# Nixie4_IN-1A_1_0.net
KiCad netlist of a schematic drawn in EAGLE
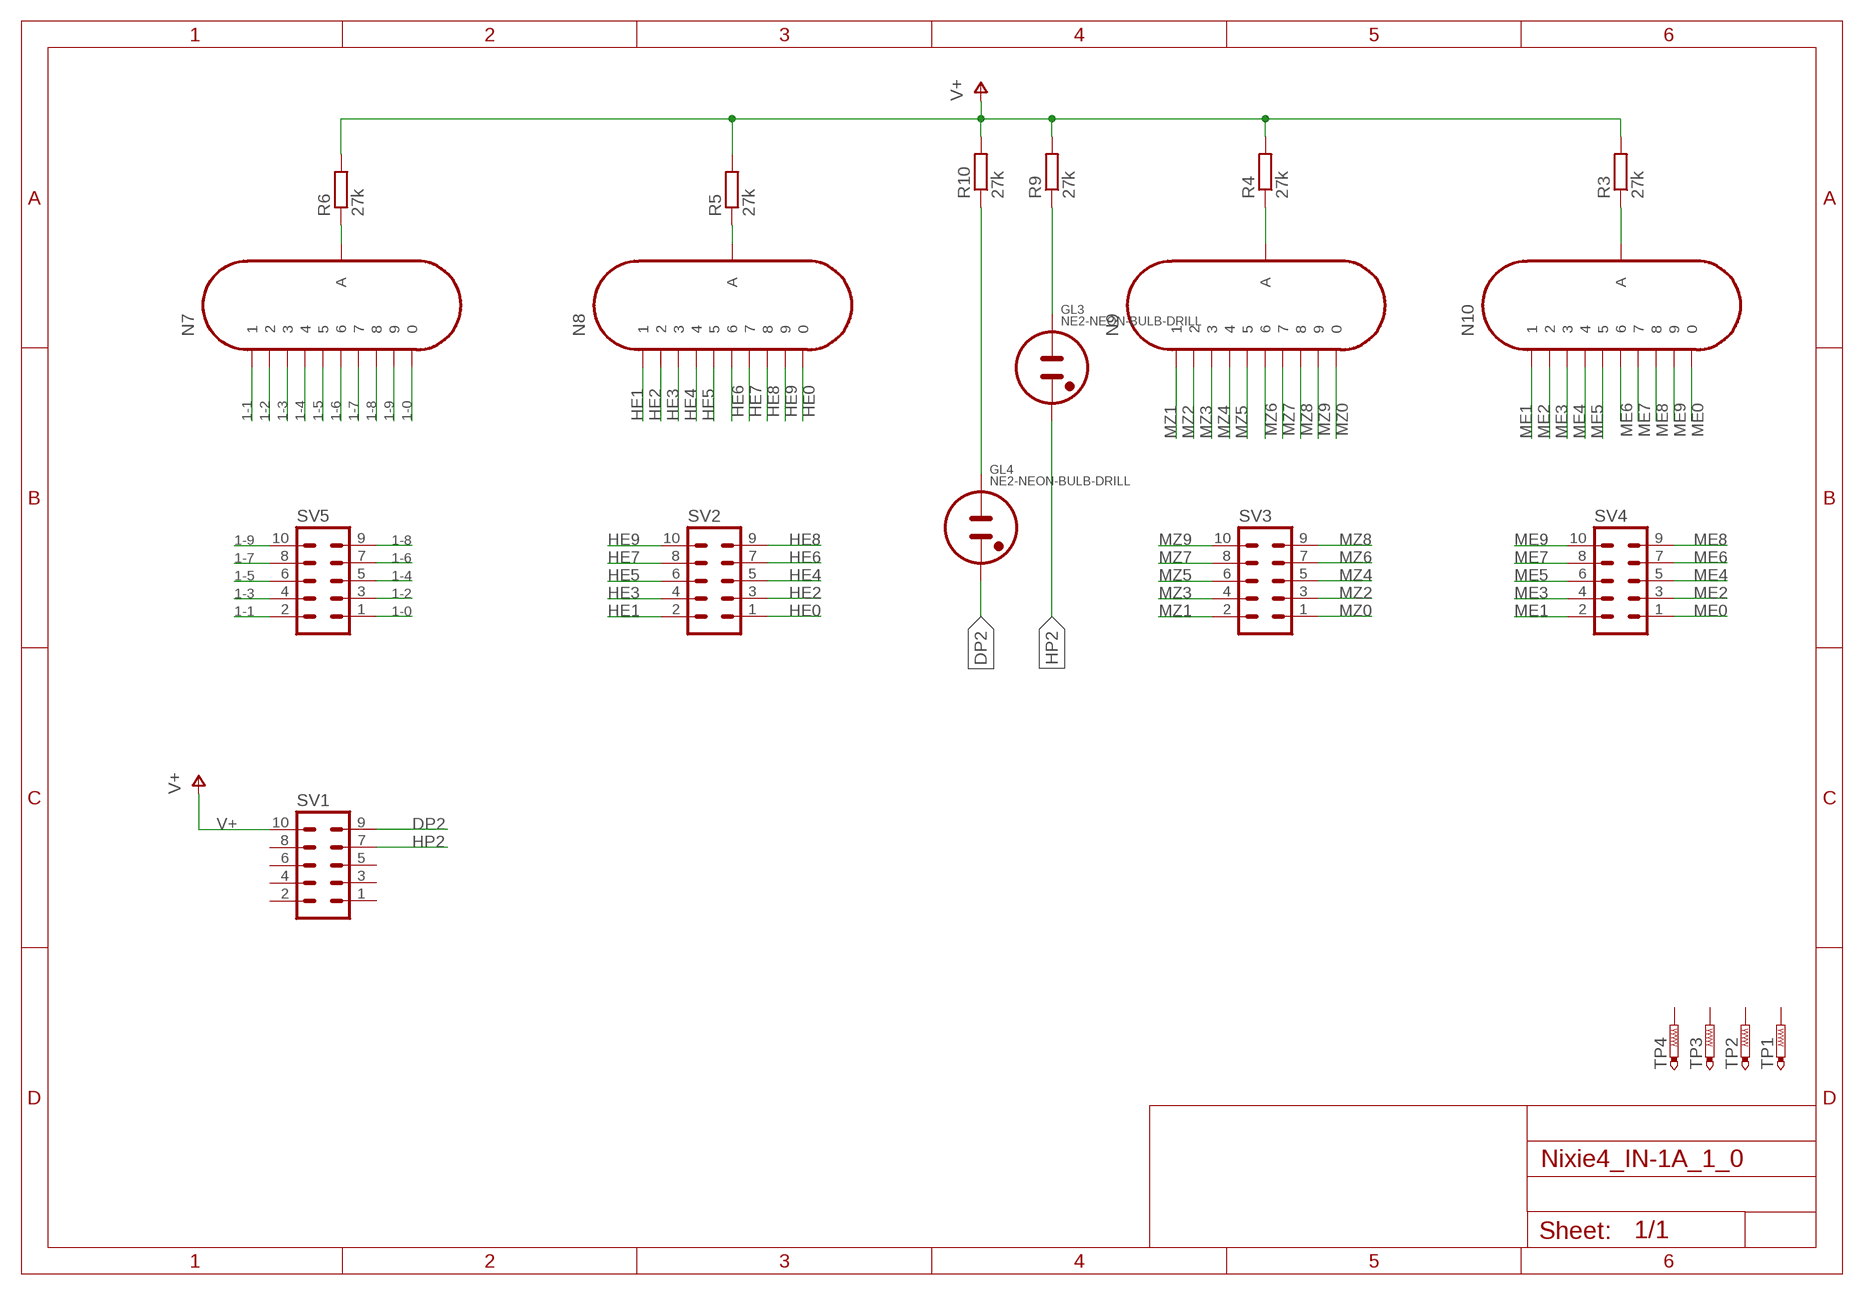
[diagram p0: schematic, sheet 1]

(export (version "E")
  (design (tool "Eeschema 10.0.6"))
  (components
    (comp (ref "GL3")
      (value "NE2-NEON-BULB-DRILL")
      (footprint "eagle-import:NE2-NEON-BULB-DRILL")
      (libsource (lib "eagle-import") (part "NE2-NEON-BULB-DRILL"))
    )
    (comp (ref "GL4")
      (value "NE2-NEON-BULB-DRILL")
      (footprint "eagle-import:NE2-NEON-BULB-DRILL")
      (libsource (lib "eagle-import") (part "NE2-NEON-BULB-DRILL"))
    )
    (comp (ref "N7")
      (value "IN-1A")
      (footprint "eagle-import:IN-1A")
      (libsource (lib "eagle-import") (part "IN-1A"))
    )
    (comp (ref "N8")
      (value "IN-1A")
      (footprint "eagle-import:IN-1A")
      (libsource (lib "eagle-import") (part "IN-1A"))
    )
    (comp (ref "N9")
      (value "IN-1A")
      (footprint "eagle-import:IN-1A")
      (libsource (lib "eagle-import") (part "IN-1A"))
    )
    (comp (ref "N10")
      (value "IN-1A")
      (footprint "eagle-import:IN-1A")
      (libsource (lib "eagle-import") (part "IN-1A"))
    )
    (comp (ref "R3")
      (value "27k")
      (footprint "eagle-import:0207_10")
      (libsource (lib "eagle-import") (part "R-EU_0207/10"))
    )
    (comp (ref "R4")
      (value "27k")
      (footprint "eagle-import:0207_10")
      (libsource (lib "eagle-import") (part "R-EU_0207/10"))
    )
    (comp (ref "R5")
      (value "27k")
      (footprint "eagle-import:0207_10")
      (libsource (lib "eagle-import") (part "R-EU_0207/10"))
    )
    (comp (ref "R6")
      (value "27k")
      (footprint "eagle-import:0207_10")
      (libsource (lib "eagle-import") (part "R-EU_0207/10"))
    )
    (comp (ref "R9")
      (value "27k")
      (footprint "eagle-import:0207_10")
      (libsource (lib "eagle-import") (part "R-EU_0207/10"))
    )
    (comp (ref "R10")
      (value "27k")
      (footprint "eagle-import:0207_10")
      (libsource (lib "eagle-import") (part "R-EU_0207/10"))
    )
    (comp (ref "SV1")
      (value "ML10")
      (footprint "eagle-import:ML10")
      (libsource (lib "eagle-import") (part "ML10"))
    )
    (comp (ref "SV2")
      (value "ML10")
      (footprint "eagle-import:ML10")
      (libsource (lib "eagle-import") (part "ML10"))
    )
    (comp (ref "SV3")
      (value "ML10")
      (footprint "eagle-import:ML10")
      (libsource (lib "eagle-import") (part "ML10"))
    )
    (comp (ref "SV4")
      (value "ML10")
      (footprint "eagle-import:ML10")
      (libsource (lib "eagle-import") (part "ML10"))
    )
    (comp (ref "SV5")
      (value "ML10")
      (footprint "eagle-import:ML10")
      (libsource (lib "eagle-import") (part "ML10"))
    )
    (comp (ref "TP1")
      (value "PTR1B1,27")
      (footprint "eagle-import:B1,27")
      (libsource (lib "eagle-import") (part "PTR1B1,27"))
    )
    (comp (ref "TP2")
      (value "PTR1B1,27")
      (footprint "eagle-import:B1,27")
      (libsource (lib "eagle-import") (part "PTR1B1,27"))
    )
    (comp (ref "TP3")
      (value "PTR1B1,27")
      (footprint "eagle-import:B1,27")
      (libsource (lib "eagle-import") (part "PTR1B1,27"))
    )
    (comp (ref "TP4")
      (value "PTR1B1,27")
      (footprint "eagle-import:B1,27")
      (libsource (lib "eagle-import") (part "PTR1B1,27"))
    )
  )
  (nets
    (net (code "1") (name "/1-0") (class "Default")
      (node (ref "N7") (pin "0") (pinfunction "0_0") (pintype "bidirectional"))
      (node (ref "SV5") (pin "1") (pinfunction "1_1") (pintype "passive"))
    )
    (net (code "2") (name "/1-1") (class "Default")
      (node (ref "N7") (pin "1") (pinfunction "1_1") (pintype "bidirectional"))
      (node (ref "SV5") (pin "2") (pinfunction "2_2") (pintype "passive"))
    )
    (net (code "3") (name "/1-2") (class "Default")
      (node (ref "N7") (pin "2") (pinfunction "2_2") (pintype "bidirectional"))
      (node (ref "SV5") (pin "3") (pinfunction "3_3") (pintype "passive"))
    )
    (net (code "4") (name "/1-3") (class "Default")
      (node (ref "N7") (pin "3") (pinfunction "3_3") (pintype "bidirectional"))
      (node (ref "SV5") (pin "4") (pinfunction "4_4") (pintype "passive"))
    )
    (net (code "5") (name "/1-4") (class "Default")
      (node (ref "N7") (pin "4") (pinfunction "4_4") (pintype "bidirectional"))
      (node (ref "SV5") (pin "5") (pinfunction "5_5") (pintype "passive"))
    )
    (net (code "6") (name "/1-5") (class "Default")
      (node (ref "N7") (pin "5") (pinfunction "5_5") (pintype "bidirectional"))
      (node (ref "SV5") (pin "6") (pinfunction "6_6") (pintype "passive"))
    )
    (net (code "7") (name "/1-6") (class "Default")
      (node (ref "N7") (pin "6") (pinfunction "6_6") (pintype "bidirectional"))
      (node (ref "SV5") (pin "7") (pinfunction "7_7") (pintype "passive"))
    )
    (net (code "8") (name "/1-7") (class "Default")
      (node (ref "N7") (pin "7") (pinfunction "7_7") (pintype "bidirectional"))
      (node (ref "SV5") (pin "8") (pinfunction "8_8") (pintype "passive"))
    )
    (net (code "9") (name "/1-8") (class "Default")
      (node (ref "N7") (pin "8") (pinfunction "8_8") (pintype "bidirectional"))
      (node (ref "SV5") (pin "9") (pinfunction "9_9") (pintype "passive"))
    )
    (net (code "10") (name "/1-9") (class "Default")
      (node (ref "N7") (pin "9") (pinfunction "9_9") (pintype "bidirectional"))
      (node (ref "SV5") (pin "10") (pinfunction "10_10") (pintype "passive"))
    )
    (net (code "11") (name "/HE0") (class "Default")
      (node (ref "N8") (pin "0") (pinfunction "0_0") (pintype "bidirectional"))
      (node (ref "SV2") (pin "1") (pinfunction "1_1") (pintype "passive"))
    )
    (net (code "12") (name "/HE1") (class "Default")
      (node (ref "N8") (pin "1") (pinfunction "1_1") (pintype "bidirectional"))
      (node (ref "SV2") (pin "2") (pinfunction "2_2") (pintype "passive"))
    )
    (net (code "13") (name "/HE2") (class "Default")
      (node (ref "N8") (pin "2") (pinfunction "2_2") (pintype "bidirectional"))
      (node (ref "SV2") (pin "3") (pinfunction "3_3") (pintype "passive"))
    )
    (net (code "14") (name "/HE3") (class "Default")
      (node (ref "N8") (pin "3") (pinfunction "3_3") (pintype "bidirectional"))
      (node (ref "SV2") (pin "4") (pinfunction "4_4") (pintype "passive"))
    )
    (net (code "15") (name "/HE4") (class "Default")
      (node (ref "N8") (pin "4") (pinfunction "4_4") (pintype "bidirectional"))
      (node (ref "SV2") (pin "5") (pinfunction "5_5") (pintype "passive"))
    )
    (net (code "16") (name "/HE5") (class "Default")
      (node (ref "N8") (pin "5") (pinfunction "5_5") (pintype "bidirectional"))
      (node (ref "SV2") (pin "6") (pinfunction "6_6") (pintype "passive"))
    )
    (net (code "17") (name "/HE6") (class "Default")
      (node (ref "N8") (pin "6") (pinfunction "6_6") (pintype "bidirectional"))
      (node (ref "SV2") (pin "7") (pinfunction "7_7") (pintype "passive"))
    )
    (net (code "18") (name "/HE7") (class "Default")
      (node (ref "N8") (pin "7") (pinfunction "7_7") (pintype "bidirectional"))
      (node (ref "SV2") (pin "8") (pinfunction "8_8") (pintype "passive"))
    )
    (net (code "19") (name "/HE8") (class "Default")
      (node (ref "N8") (pin "8") (pinfunction "8_8") (pintype "bidirectional"))
      (node (ref "SV2") (pin "9") (pinfunction "9_9") (pintype "passive"))
    )
    (net (code "20") (name "/HE9") (class "Default")
      (node (ref "N8") (pin "9") (pinfunction "9_9") (pintype "bidirectional"))
      (node (ref "SV2") (pin "10") (pinfunction "10_10") (pintype "passive"))
    )
    (net (code "21") (name "/ME0") (class "Default")
      (node (ref "N10") (pin "0") (pinfunction "0_0") (pintype "bidirectional"))
      (node (ref "SV4") (pin "1") (pinfunction "1_1") (pintype "passive"))
    )
    (net (code "22") (name "/ME1") (class "Default")
      (node (ref "N10") (pin "1") (pinfunction "1_1") (pintype "bidirectional"))
      (node (ref "SV4") (pin "2") (pinfunction "2_2") (pintype "passive"))
    )
    (net (code "23") (name "/ME2") (class "Default")
      (node (ref "N10") (pin "2") (pinfunction "2_2") (pintype "bidirectional"))
      (node (ref "SV4") (pin "3") (pinfunction "3_3") (pintype "passive"))
    )
    (net (code "24") (name "/ME3") (class "Default")
      (node (ref "N10") (pin "3") (pinfunction "3_3") (pintype "bidirectional"))
      (node (ref "SV4") (pin "4") (pinfunction "4_4") (pintype "passive"))
    )
    (net (code "25") (name "/ME4") (class "Default")
      (node (ref "N10") (pin "4") (pinfunction "4_4") (pintype "bidirectional"))
      (node (ref "SV4") (pin "5") (pinfunction "5_5") (pintype "passive"))
    )
    (net (code "26") (name "/ME5") (class "Default")
      (node (ref "N10") (pin "5") (pinfunction "5_5") (pintype "bidirectional"))
      (node (ref "SV4") (pin "6") (pinfunction "6_6") (pintype "passive"))
    )
    (net (code "27") (name "/ME6") (class "Default")
      (node (ref "N10") (pin "6") (pinfunction "6_6") (pintype "bidirectional"))
      (node (ref "SV4") (pin "7") (pinfunction "7_7") (pintype "passive"))
    )
    (net (code "28") (name "/ME7") (class "Default")
      (node (ref "N10") (pin "7") (pinfunction "7_7") (pintype "bidirectional"))
      (node (ref "SV4") (pin "8") (pinfunction "8_8") (pintype "passive"))
    )
    (net (code "29") (name "/ME8") (class "Default")
      (node (ref "N10") (pin "8") (pinfunction "8_8") (pintype "bidirectional"))
      (node (ref "SV4") (pin "9") (pinfunction "9_9") (pintype "passive"))
    )
    (net (code "30") (name "/ME9") (class "Default")
      (node (ref "N10") (pin "9") (pinfunction "9_9") (pintype "bidirectional"))
      (node (ref "SV4") (pin "10") (pinfunction "10_10") (pintype "passive"))
    )
    (net (code "31") (name "/MZ0") (class "Default")
      (node (ref "N9") (pin "0") (pinfunction "0_0") (pintype "bidirectional"))
      (node (ref "SV3") (pin "1") (pinfunction "1_1") (pintype "passive"))
    )
    (net (code "32") (name "/MZ1") (class "Default")
      (node (ref "N9") (pin "1") (pinfunction "1_1") (pintype "bidirectional"))
      (node (ref "SV3") (pin "2") (pinfunction "2_2") (pintype "passive"))
    )
    (net (code "33") (name "/MZ2") (class "Default")
      (node (ref "N9") (pin "2") (pinfunction "2_2") (pintype "bidirectional"))
      (node (ref "SV3") (pin "3") (pinfunction "3_3") (pintype "passive"))
    )
    (net (code "34") (name "/MZ3") (class "Default")
      (node (ref "N9") (pin "3") (pinfunction "3_3") (pintype "bidirectional"))
      (node (ref "SV3") (pin "4") (pinfunction "4_4") (pintype "passive"))
    )
    (net (code "35") (name "/MZ4") (class "Default")
      (node (ref "N9") (pin "4") (pinfunction "4_4") (pintype "bidirectional"))
      (node (ref "SV3") (pin "5") (pinfunction "5_5") (pintype "passive"))
    )
    (net (code "36") (name "/MZ5") (class "Default")
      (node (ref "N9") (pin "5") (pinfunction "5_5") (pintype "bidirectional"))
      (node (ref "SV3") (pin "6") (pinfunction "6_6") (pintype "passive"))
    )
    (net (code "37") (name "/MZ6") (class "Default")
      (node (ref "N9") (pin "6") (pinfunction "6_6") (pintype "bidirectional"))
      (node (ref "SV3") (pin "7") (pinfunction "7_7") (pintype "passive"))
    )
    (net (code "38") (name "/MZ7") (class "Default")
      (node (ref "N9") (pin "7") (pinfunction "7_7") (pintype "bidirectional"))
      (node (ref "SV3") (pin "8") (pinfunction "8_8") (pintype "passive"))
    )
    (net (code "39") (name "/MZ8") (class "Default")
      (node (ref "N9") (pin "8") (pinfunction "8_8") (pintype "bidirectional"))
      (node (ref "SV3") (pin "9") (pinfunction "9_9") (pintype "passive"))
    )
    (net (code "40") (name "/MZ9") (class "Default")
      (node (ref "N9") (pin "9") (pinfunction "9_9") (pintype "bidirectional"))
      (node (ref "SV3") (pin "10") (pinfunction "10_10") (pintype "passive"))
    )
    (net (code "41") (name "DP2") (class "Default")
      (node (ref "GL4") (pin "2") (pinfunction "A1_2") (pintype "passive"))
      (node (ref "SV1") (pin "9") (pinfunction "9_9") (pintype "passive"))
    )
    (net (code "42") (name "HP2") (class "Default")
      (node (ref "GL3") (pin "2") (pinfunction "A1_2") (pintype "passive"))
      (node (ref "SV1") (pin "7") (pinfunction "7_7") (pintype "passive"))
    )
    (net (code "43") (name "Net-(GL3-A)") (class "Default")
      (node (ref "GL3") (pin "1") (pinfunction "A_1") (pintype "passive"))
      (node (ref "R9") (pin "1") (pinfunction "1_1") (pintype "passive"))
    )
    (net (code "44") (name "Net-(GL4-A)") (class "Default")
      (node (ref "GL4") (pin "1") (pinfunction "A_1") (pintype "passive"))
      (node (ref "R10") (pin "1") (pinfunction "1_1") (pintype "passive"))
    )
    (net (code "45") (name "Net-(N7-PadA)") (class "Default")
      (node (ref "N7") (pin "A") (pinfunction "A_A") (pintype "bidirectional"))
      (node (ref "R6") (pin "1") (pinfunction "1_1") (pintype "passive"))
    )
    (net (code "46") (name "Net-(N8-PadA)") (class "Default")
      (node (ref "N8") (pin "A") (pinfunction "A_A") (pintype "bidirectional"))
      (node (ref "R5") (pin "1") (pinfunction "1_1") (pintype "passive"))
    )
    (net (code "47") (name "Net-(N9-PadA)") (class "Default")
      (node (ref "N9") (pin "A") (pinfunction "A_A") (pintype "bidirectional"))
      (node (ref "R4") (pin "1") (pinfunction "1_1") (pintype "passive"))
    )
    (net (code "48") (name "Net-(N10-PadA)") (class "Default")
      (node (ref "N10") (pin "A") (pinfunction "A_A") (pintype "bidirectional"))
      (node (ref "R3") (pin "1") (pinfunction "1_1") (pintype "passive"))
    )
    (net (code "49") (name "V+") (class "Default")
      (node (ref "R10") (pin "2") (pinfunction "2_2") (pintype "passive"))
      (node (ref "R3") (pin "2") (pinfunction "2_2") (pintype "passive"))
      (node (ref "R4") (pin "2") (pinfunction "2_2") (pintype "passive"))
      (node (ref "R5") (pin "2") (pinfunction "2_2") (pintype "passive"))
      (node (ref "R6") (pin "2") (pinfunction "2_2") (pintype "passive"))
      (node (ref "R9") (pin "2") (pinfunction "2_2") (pintype "passive"))
      (node (ref "SV1") (pin "10") (pinfunction "10_10") (pintype "passive"))
    )
    (net (code "50") (name "unconnected-(SV1-Pad1)") (class "Default")
      (node (ref "SV1") (pin "1") (pinfunction "1_1") (pintype "passive"))
    )
    (net (code "51") (name "unconnected-(SV1-Pad2)") (class "Default")
      (node (ref "SV1") (pin "2") (pinfunction "2_2") (pintype "passive"))
    )
    (net (code "52") (name "unconnected-(SV1-Pad3)") (class "Default")
      (node (ref "SV1") (pin "3") (pinfunction "3_3") (pintype "passive"))
    )
    (net (code "53") (name "unconnected-(SV1-Pad4)") (class "Default")
      (node (ref "SV1") (pin "4") (pinfunction "4_4") (pintype "passive"))
    )
    (net (code "54") (name "unconnected-(SV1-Pad5)") (class "Default")
      (node (ref "SV1") (pin "5") (pinfunction "5_5") (pintype "passive"))
    )
    (net (code "55") (name "unconnected-(SV1-Pad6)") (class "Default")
      (node (ref "SV1") (pin "6") (pinfunction "6_6") (pintype "passive"))
    )
    (net (code "56") (name "unconnected-(SV1-Pad8)") (class "Default")
      (node (ref "SV1") (pin "8") (pinfunction "8_8") (pintype "passive"))
    )
    (net (code "57") (name "unconnected-(TP1-PadTP)") (class "Default")
      (node (ref "TP1") (pin "TP") (pinfunction "TP_TP") (pintype "input"))
    )
    (net (code "58") (name "unconnected-(TP2-PadTP)") (class "Default")
      (node (ref "TP2") (pin "TP") (pinfunction "TP_TP") (pintype "input"))
    )
    (net (code "59") (name "unconnected-(TP3-PadTP)") (class "Default")
      (node (ref "TP3") (pin "TP") (pinfunction "TP_TP") (pintype "input"))
    )
    (net (code "60") (name "unconnected-(TP4-PadTP)") (class "Default")
      (node (ref "TP4") (pin "TP") (pinfunction "TP_TP") (pintype "input"))
    )
  )
)
